# utilidong-ftdi-uart-mk-2_0.net
KiCad netlist of a schematic drawn in EAGLE
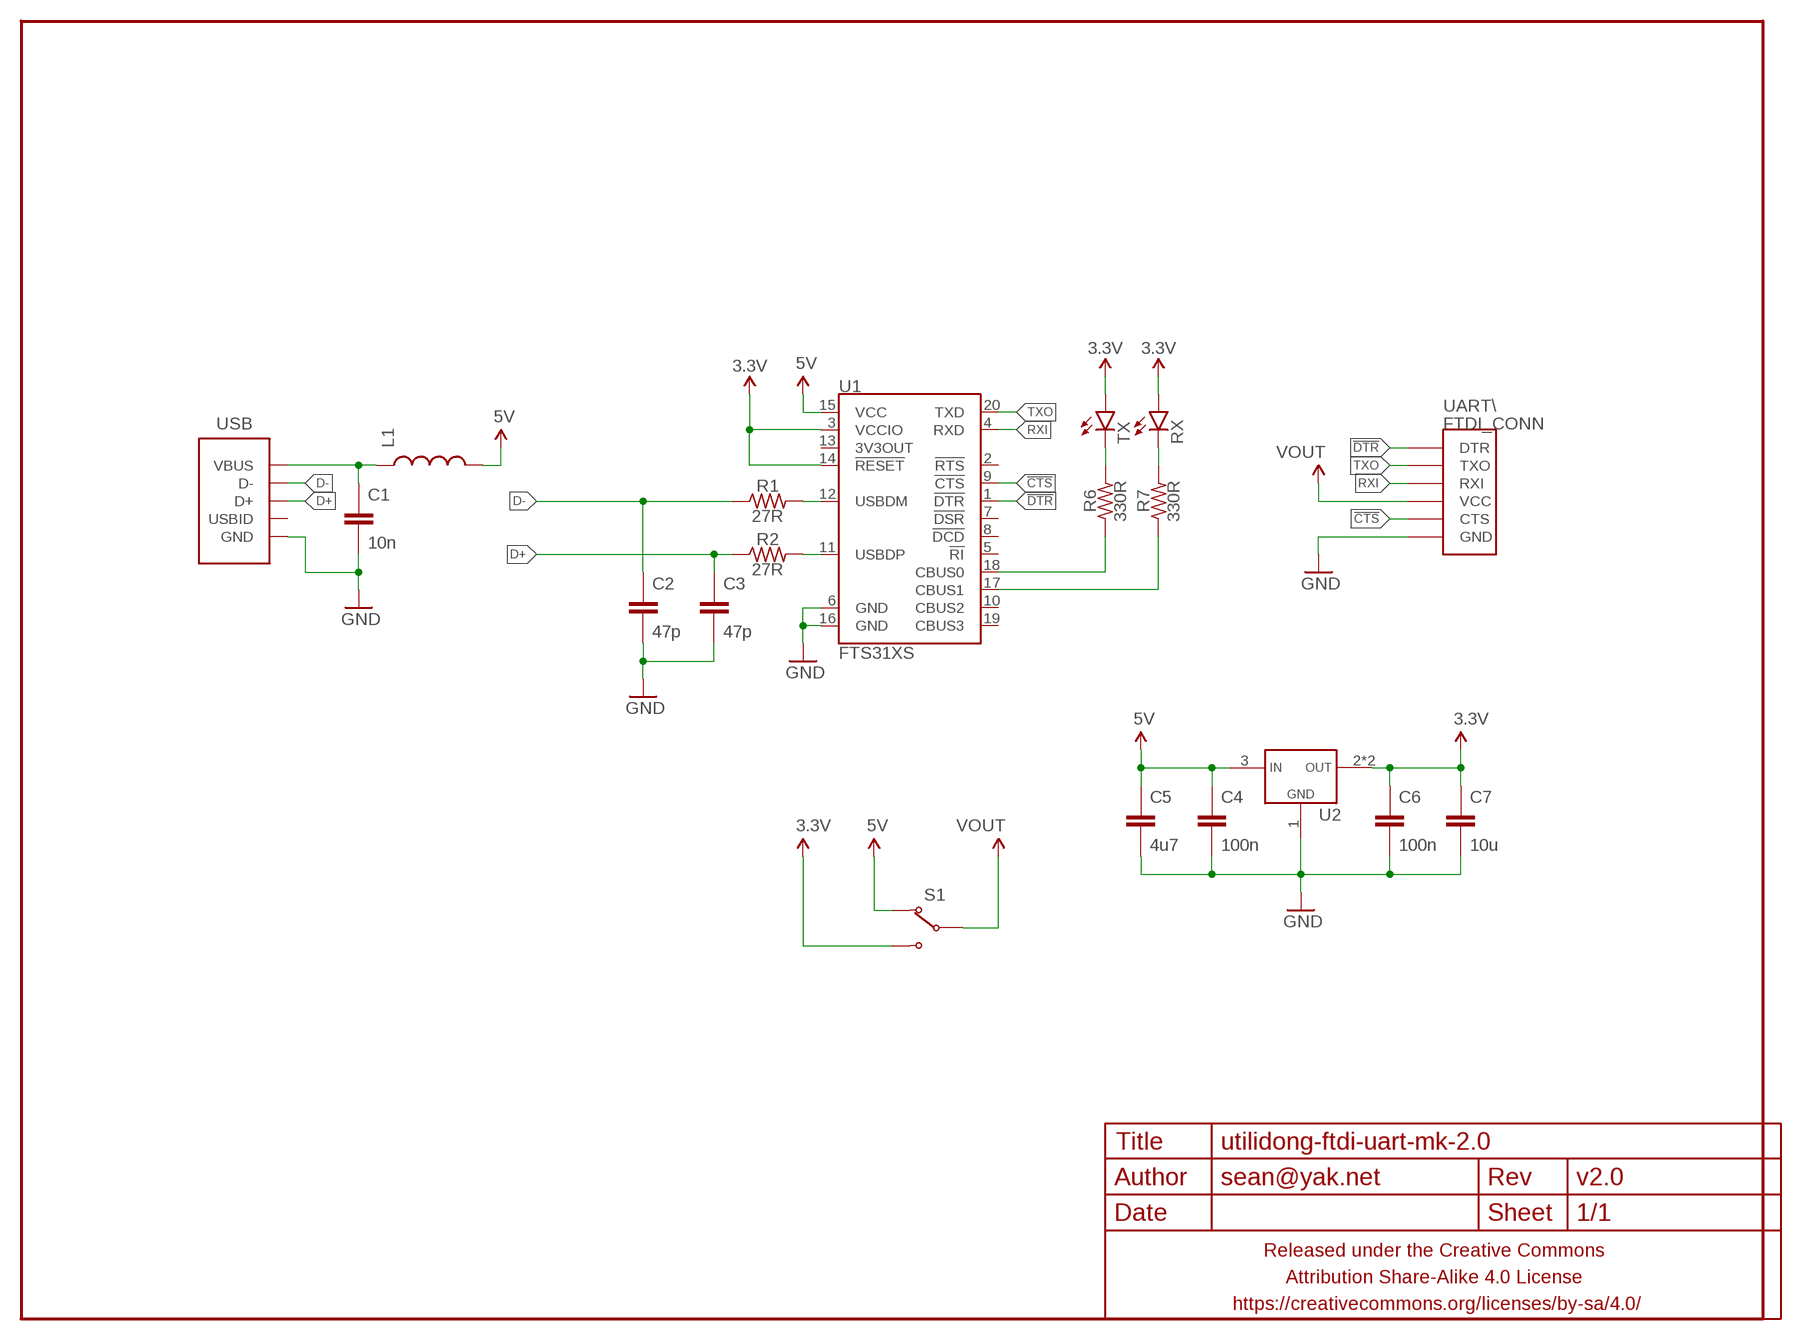
[diagram p0: schematic, sheet 1]

(export (version "E")
  (design (tool "Eeschema 10.0.6"))
  (components
    (comp (ref "C1")
      (value "10n")
      (footprint "eagle-import:C0603")
      (libsource (lib "eagle-import") (part "CAPACITOR-CERAMICC0603"))
    )
    (comp (ref "C2")
      (value "47p")
      (footprint "eagle-import:C0603")
      (libsource (lib "eagle-import") (part "CAPACITOR-CERAMICC0603"))
    )
    (comp (ref "C3")
      (value "47p")
      (footprint "eagle-import:C0603")
      (libsource (lib "eagle-import") (part "CAPACITOR-CERAMICC0603"))
    )
    (comp (ref "C4")
      (value "100n")
      (footprint "eagle-import:C0603")
      (libsource (lib "eagle-import") (part "CAPACITOR-CERAMICC0603"))
    )
    (comp (ref "C5")
      (value "4u7")
      (footprint "eagle-import:C0603")
      (libsource (lib "eagle-import") (part "CAPACITOR-CERAMICC0603"))
    )
    (comp (ref "C6")
      (value "100n")
      (footprint "eagle-import:C0603")
      (libsource (lib "eagle-import") (part "CAPACITOR-CERAMICC0603"))
    )
    (comp (ref "C7")
      (value "10u")
      (footprint "eagle-import:C0805")
      (libsource (lib "eagle-import") (part "CAPACITOR-CERAMICC0805"))
    )
    (comp (ref "FRAME1")
      (value "FRAME-LETTERNO_PACKAGE")
      (footprint "eagle-import:DUMMY")
      (fields (field (name "DESIGNER") "sean@yak.net") (field (name "VERSION") "v2.0"))
      (libsource (lib "eagle-import") (part "FRAME-LETTERNO_PACKAGE"))
    )
    (comp (ref "L1")
      (value "INDUCTOR0603")
      (footprint "eagle-import:0603")
      (libsource (lib "eagle-import") (part "INDUCTOR0603"))
    )
    (comp (ref "R1")
      (value "27R")
      (footprint "eagle-import:R0603")
      (libsource (lib "eagle-import") (part "RESISTORR0603"))
    )
    (comp (ref "R2")
      (value "27R")
      (footprint "eagle-import:R0603")
      (libsource (lib "eagle-import") (part "RESISTORR0603"))
    )
    (comp (ref "R6")
      (value "330R")
      (footprint "eagle-import:R0603")
      (libsource (lib "eagle-import") (part "RESISTORR0603"))
    )
    (comp (ref "R7")
      (value "330R")
      (footprint "eagle-import:R0603")
      (libsource (lib "eagle-import") (part "RESISTORR0603"))
    )
    (comp (ref "RX")
      (value "LED0603")
      (footprint "eagle-import:LED-0603")
      (libsource (lib "eagle-import") (part "LED0603"))
    )
    (comp (ref "S1")
      (value "SWITCH-SPDTSMD-RA")
      (footprint "eagle-import:SWITCH-SPDT-SMD-RA")
      (libsource (lib "eagle-import") (part "SWITCH-SPDTSMD-RA"))
    )
    (comp (ref "TX")
      (value "LED0603")
      (footprint "eagle-import:LED-0603")
      (libsource (lib "eagle-import") (part "LED0603"))
    )
    (comp (ref "U1")
      (value "FTS31XS")
      (footprint "eagle-import:SSOP20_L")
      (libsource (lib "eagle-import") (part "FT231XS"))
    )
    (comp (ref "U2")
      (value "VREG_1117SOT89")
      (footprint "eagle-import:SOT89")
      (libsource (lib "eagle-import") (part "VREG_1117SOT89"))
    )
    (comp (ref "UART\\")
      (value "FTDI_CONN")
      (footprint "eagle-import:FTDI_CONN")
      (libsource (lib "eagle-import") (part "FTDI_CONN"))
    )
    (comp (ref "USB")
      (value "USB-ABFCI-10103594-USB-MICRO-B-LESS")
      (footprint "eagle-import:FCI-10103594-USB-MICRO-B-LESS")
      (libsource (lib "eagle-import") (part "USB-ABFCI-10103594-USB-MICRO-B-LESS"))
    )
  )
  (nets
    (net (code "1") (name "/~{CTS}") (class "Default")
      (node (ref "U1") (pin "9") (pinfunction "~{CTS}_9") (pintype "bidirectional"))
      (node (ref "UART\\") (pin "CTS") (pinfunction "CTS_CTS") (pintype "bidirectional"))
    )
    (net (code "2") (name "/~{DTR}") (class "Default")
      (node (ref "U1") (pin "1") (pinfunction "~{DTR}_1") (pintype "bidirectional"))
      (node (ref "UART\\") (pin "DTR") (pinfunction "DTR_DTR") (pintype "bidirectional"))
    )
    (net (code "3") (name "3.3V") (class "Default")
      (node (ref "C6") (pin "1") (pinfunction "1_1") (pintype "passive"))
      (node (ref "C7") (pin "1") (pinfunction "1_1") (pintype "passive"))
      (node (ref "RX") (pin "A") (pinfunction "A_A") (pintype "passive"))
      (node (ref "S1") (pin "1") (pinfunction "NO_1") (pintype "passive"))
      (node (ref "TX") (pin "A") (pinfunction "A_A") (pintype "passive"))
      (node (ref "U1") (pin "14") (pinfunction "~{RESET}_14") (pintype "bidirectional"))
      (node (ref "U1") (pin "3") (pinfunction "VCCIO_3") (pintype "bidirectional"))
      (node (ref "U2") (pin "2") (pinfunction "VOUT_2") (pintype "bidirectional"))
      (node (ref "U2") (pin "4") (pinfunction "VOUT_4") (pintype "bidirectional"))
    )
    (net (code "4") (name "5V") (class "Default")
      (node (ref "C4") (pin "1") (pinfunction "1_1") (pintype "passive"))
      (node (ref "C5") (pin "1") (pinfunction "1_1") (pintype "passive"))
      (node (ref "L1") (pin "2") (pinfunction "2_2") (pintype "passive"))
      (node (ref "S1") (pin "3") (pinfunction "NC_3") (pintype "passive"))
      (node (ref "U1") (pin "15") (pinfunction "VCC_15") (pintype "bidirectional"))
      (node (ref "U2") (pin "3") (pinfunction "VIN_3") (pintype "bidirectional"))
    )
    (net (code "5") (name "D+") (class "Default")
      (node (ref "C3") (pin "1") (pinfunction "1_1") (pintype "passive"))
      (node (ref "R2") (pin "1") (pinfunction "1_1") (pintype "passive"))
      (node (ref "USB") (pin "3") (pinfunction "D+_3") (pintype "bidirectional"))
    )
    (net (code "6") (name "D-") (class "Default")
      (node (ref "C2") (pin "1") (pinfunction "1_1") (pintype "passive"))
      (node (ref "R1") (pin "1") (pinfunction "1_1") (pintype "passive"))
      (node (ref "USB") (pin "2") (pinfunction "D-_2") (pintype "bidirectional"))
    )
    (net (code "7") (name "GND") (class "Default")
      (node (ref "C1") (pin "2") (pinfunction "2_2") (pintype "passive"))
      (node (ref "C2") (pin "2") (pinfunction "2_2") (pintype "passive"))
      (node (ref "C3") (pin "2") (pinfunction "2_2") (pintype "passive"))
      (node (ref "C4") (pin "2") (pinfunction "2_2") (pintype "passive"))
      (node (ref "C5") (pin "2") (pinfunction "2_2") (pintype "passive"))
      (node (ref "C6") (pin "2") (pinfunction "2_2") (pintype "passive"))
      (node (ref "C7") (pin "2") (pinfunction "2_2") (pintype "passive"))
      (node (ref "U1") (pin "16") (pinfunction "GND_16") (pintype "bidirectional"))
      (node (ref "U1") (pin "6") (pinfunction "GND_6") (pintype "bidirectional"))
      (node (ref "U2") (pin "1") (pinfunction "GND_1") (pintype "bidirectional"))
      (node (ref "UART\\") (pin "GND") (pinfunction "GND_GND") (pintype "bidirectional"))
      (node (ref "USB") (pin "5") (pinfunction "GND_5") (pintype "bidirectional"))
    )
    (net (code "8") (name "Net-(R6-Pad2)") (class "Default")
      (node (ref "R6") (pin "2") (pinfunction "2_2") (pintype "passive"))
      (node (ref "TX") (pin "C") (pinfunction "C_C") (pintype "passive"))
    )
    (net (code "9") (name "Net-(R7-Pad2)") (class "Default")
      (node (ref "R7") (pin "2") (pinfunction "2_2") (pintype "passive"))
      (node (ref "RX") (pin "C") (pinfunction "C_C") (pintype "passive"))
    )
    (net (code "10") (name "Net-(U1-CBUS0)") (class "Default")
      (node (ref "R6") (pin "1") (pinfunction "1_1") (pintype "passive"))
      (node (ref "U1") (pin "18") (pinfunction "CBUS0_18") (pintype "bidirectional"))
    )
    (net (code "11") (name "Net-(U1-CBUS1)") (class "Default")
      (node (ref "R7") (pin "1") (pinfunction "1_1") (pintype "passive"))
      (node (ref "U1") (pin "17") (pinfunction "CBUS1_17") (pintype "bidirectional"))
    )
    (net (code "12") (name "Net-(U1-USBDM)") (class "Default")
      (node (ref "R1") (pin "2") (pinfunction "2_2") (pintype "passive"))
      (node (ref "U1") (pin "12") (pinfunction "USBDM_12") (pintype "bidirectional"))
    )
    (net (code "13") (name "Net-(U1-USBDP)") (class "Default")
      (node (ref "R2") (pin "2") (pinfunction "2_2") (pintype "passive"))
      (node (ref "U1") (pin "11") (pinfunction "USBDP_11") (pintype "bidirectional"))
    )
    (net (code "14") (name "Net-(USB-VBUS)") (class "Default")
      (node (ref "C1") (pin "1") (pinfunction "1_1") (pintype "passive"))
      (node (ref "L1") (pin "1") (pinfunction "1_1") (pintype "passive"))
      (node (ref "USB") (pin "1") (pinfunction "VBUS_1") (pintype "bidirectional"))
    )
    (net (code "15") (name "RXI") (class "Default")
      (node (ref "U1") (pin "4") (pinfunction "RXD_4") (pintype "bidirectional"))
      (node (ref "UART\\") (pin "RXI") (pinfunction "RXI_RXI") (pintype "bidirectional"))
    )
    (net (code "16") (name "TXO") (class "Default")
      (node (ref "U1") (pin "20") (pinfunction "TXD_20") (pintype "bidirectional"))
      (node (ref "UART\\") (pin "TXO") (pinfunction "TXO_TXO") (pintype "bidirectional"))
    )
    (net (code "17") (name "VOUT") (class "Default")
      (node (ref "S1") (pin "2") (pinfunction "COM_2") (pintype "passive"))
      (node (ref "UART\\") (pin "VCC") (pinfunction "VCC_VCC") (pintype "bidirectional"))
    )
    (net (code "18") (name "unconnected-(U1-3V3OUT-Pad13)") (class "Default")
      (node (ref "U1") (pin "13") (pinfunction "3V3OUT_13") (pintype "bidirectional"))
    )
    (net (code "19") (name "unconnected-(U1-CBUS2-Pad10)") (class "Default")
      (node (ref "U1") (pin "10") (pinfunction "CBUS2_10") (pintype "bidirectional"))
    )
    (net (code "20") (name "unconnected-(U1-CBUS3-Pad19)") (class "Default")
      (node (ref "U1") (pin "19") (pinfunction "CBUS3_19") (pintype "bidirectional"))
    )
    (net (code "21") (name "unconnected-(U1-~{DCD}-Pad8)") (class "Default")
      (node (ref "U1") (pin "8") (pinfunction "~{DCD}_8") (pintype "bidirectional"))
    )
    (net (code "22") (name "unconnected-(U1-~{DSR}-Pad7)") (class "Default")
      (node (ref "U1") (pin "7") (pinfunction "~{DSR}_7") (pintype "bidirectional"))
    )
    (net (code "23") (name "unconnected-(U1-~{RI}-Pad5)") (class "Default")
      (node (ref "U1") (pin "5") (pinfunction "~{RI}_5") (pintype "bidirectional"))
    )
    (net (code "24") (name "unconnected-(U1-~{RTS}-Pad2)") (class "Default")
      (node (ref "U1") (pin "2") (pinfunction "~{RTS}_2") (pintype "bidirectional"))
    )
    (net (code "25") (name "unconnected-(USB-USBID-Pad4)") (class "Default")
      (node (ref "USB") (pin "4") (pinfunction "USBID_4") (pintype "bidirectional"))
    )
  )
)
